# Sheet1.net
KiCad netlist of a schematic drawn in Altium Designer
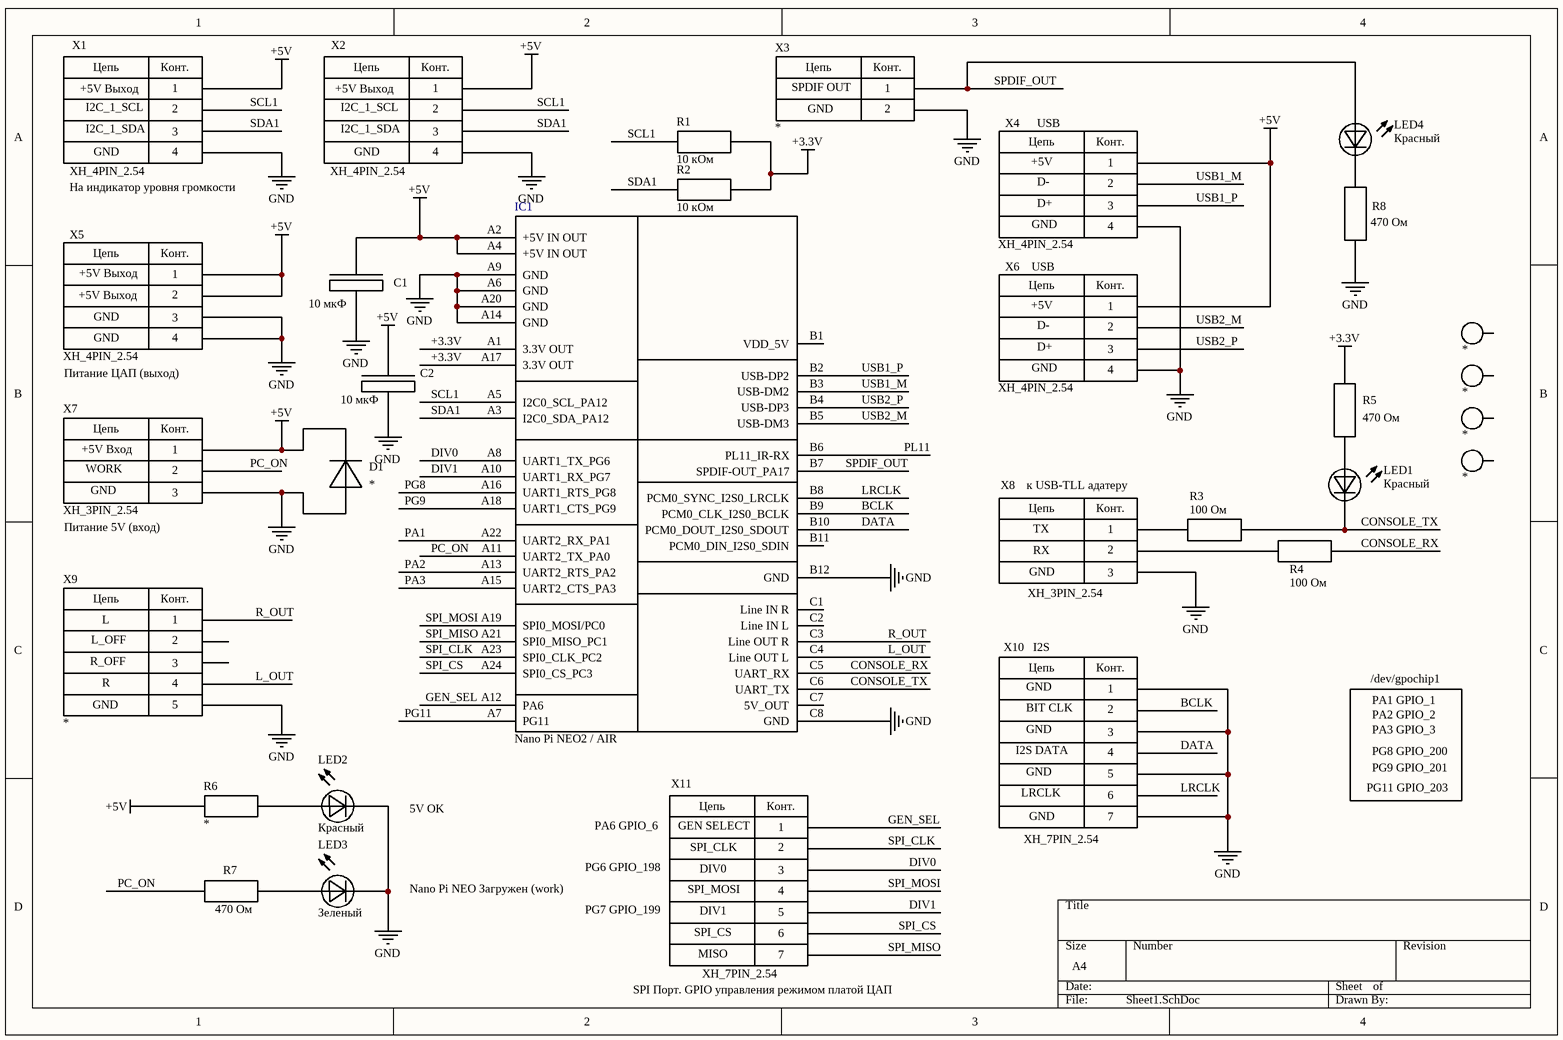
[diagram p0: Sheet1.SchDoc]

(export (version "E")
  (design (tool "Eeschema 10.0.6"))
  (components
    (comp (ref "C1")
      (value "10 мкФ")
      (footprint "Конденсатор SMD тантал 4x7")
      (libsource (lib "S83") (part "Конденсатор"))
    )
    (comp (ref "C2")
      (value "10 мкФ")
      (footprint "Конденсатор SMD тантал 4x7")
      (libsource (lib "S83") (part "Конденсатор"))
    )
    (comp (ref "D1") (value "*") (footprint "Диод SS14") (libsource (lib "S83") (part "Диод")))
    (comp (ref "H1")
      (value "*")
      (footprint "Отверстие 3,2")
      (libsource (lib "S83") (part "Отверстие монтажное"))
    )
    (comp (ref "H2")
      (value "*")
      (footprint "Отверстие 3,2")
      (libsource (lib "S83") (part "Отверстие монтажное"))
    )
    (comp (ref "H3")
      (value "*")
      (footprint "Отверстие 3,2")
      (libsource (lib "S83") (part "Отверстие монтажное"))
    )
    (comp (ref "H4")
      (value "*")
      (footprint "Отверстие 3,2")
      (libsource (lib "S83") (part "Отверстие монтажное"))
    )
    (comp (ref "IC1")
      (value "Nano Pi NEO2 / AIR")
      (footprint "NANOPI_NEO")
      (libsource (lib "S83_IC") (part "NanoPi NEO"))
    )
    (comp (ref "LED1")
      (value "Красный")
      (footprint "Светодиод 3mm")
      (libsource (lib "S83") (part "Светодиод"))
    )
    (comp (ref "LED2")
      (value "Красный")
      (footprint "Светодиод 3mm")
      (libsource (lib "S83") (part "Светодиод"))
    )
    (comp (ref "LED3")
      (value "Зеленый")
      (footprint "Светодиод 3mm")
      (libsource (lib "S83") (part "Светодиод"))
    )
    (comp (ref "LED4")
      (value "Красный")
      (footprint "Светодиод 3mm")
      (libsource (lib "S83") (part "Светодиод"))
    )
    (comp (ref "R1")
      (value "10 кОм")
      (footprint "SMD 1206 Резистор")
      (libsource (lib "S83") (part "Резистор"))
    )
    (comp (ref "R2")
      (value "10 кОм")
      (footprint "SMD 1206 Резистор")
      (libsource (lib "S83") (part "Резистор"))
    )
    (comp (ref "R3")
      (value "100 Ом")
      (footprint "SMD 1206 Резистор")
      (libsource (lib "S83") (part "Резистор"))
    )
    (comp (ref "R4")
      (value "100 Ом")
      (footprint "SMD 1206 Резистор")
      (libsource (lib "S83") (part "Резистор"))
    )
    (comp (ref "R5")
      (value "470 Ом")
      (footprint "SMD 1206 Резистор")
      (libsource (lib "S83") (part "Резистор"))
    )
    (comp (ref "R6") (value "*") (footprint "SMD 1206 Резистор") (libsource (lib "S83") (part "Резистор")))
    (comp (ref "R7")
      (value "470 Ом")
      (footprint "SMD 1206 Резистор")
      (libsource (lib "S83") (part "Резистор"))
    )
    (comp (ref "R8")
      (value "470 Ом")
      (footprint "SMD 1206 Резистор")
      (libsource (lib "S83") (part "Резистор"))
    )
    (comp (ref "X1")
      (value "XH_4PIN_2.54")
      (footprint "(1x4) PIN XH 2.54 HEADR")
      (libsource (lib "S83_connectors") (part "(1x4) pin XH 2.54 Header"))
    )
    (comp (ref "X2")
      (value "XH_4PIN_2.54")
      (footprint "(1x4) PIN XH 2.54 HEADR")
      (libsource (lib "S83_connectors") (part "(1x4) pin XH 2.54 Header"))
    )
    (comp (ref "X3")
      (value "*")
      (footprint "(1x2) PIN XH 2.54 header")
      (libsource (lib "S83_connectors") (part "(1x2)pin 2.54 Header"))
    )
    (comp (ref "X4")
      (value "XH_4PIN_2.54")
      (footprint "(1x4) PIN XH 2.54 HEADR")
      (libsource (lib "S83_connectors") (part "(1x4) pin XH 2.54 Header"))
    )
    (comp (ref "X5")
      (value "XH_4PIN_2.54")
      (footprint "(1x4) PIN XH 2.54 HEADR")
      (libsource (lib "S83_connectors") (part "(1x4) pin XH 2.54 Header"))
    )
    (comp (ref "X6")
      (value "XH_4PIN_2.54")
      (footprint "(1x4) PIN XH 2.54 HEADR")
      (libsource (lib "S83_connectors") (part "(1x4) pin XH 2.54 Header"))
    )
    (comp (ref "X7")
      (value "XH_3PIN_2.54")
      (footprint "(1x3) PIN XH 2.54 HEADR")
      (libsource (lib "S83_connectors") (part "(1x3)pin 2.54 Header"))
    )
    (comp (ref "X8")
      (value "XH_3PIN_2.54")
      (footprint "(1x3) PIN XH 2.54 HEADR")
      (libsource (lib "S83_connectors") (part "(1x3)pin 2.54 Header"))
    )
    (comp (ref "X9")
      (value "*")
      (footprint "3.5 Audio jack mama")
      (libsource (lib "S83_connectors") (part "3.5 Audio"))
    )
    (comp (ref "X10")
      (value "XH_7PIN_2.54")
      (footprint "(1x7) PIN XH 2.54 HEADR")
      (libsource (lib "S83_connectors") (part "(1x7) pin 2.54 Header"))
    )
    (comp (ref "X11")
      (value "XH_7PIN_2.54")
      (footprint "(1x7) PIN XH 2.54 HEADR")
      (libsource (lib "S83_connectors") (part "(1x7) pin 2.54 Header"))
    )
  )
  (nets
    (net (code "1") (name "+3.3V") (class "Default")
      (node (ref "IC1") (pin "A1") (pinfunction "3.3V_OUT_A1") (pintype "passive"))
      (node (ref "IC1") (pin "A17") (pinfunction "3.3V_OUT_A17") (pintype "passive"))
      (node (ref "R1") (pin "1") (pinfunction "left_1") (pintype "passive"))
      (node (ref "R2") (pin "1") (pinfunction "left_1") (pintype "passive"))
      (node (ref "R5") (pin "1") (pinfunction "left_1") (pintype "passive"))
    )
    (net (code "2") (name "+5V") (class "Default")
      (node (ref "C1") (pin "1") (pinfunction "1_1") (pintype "passive"))
      (node (ref "C2") (pin "1") (pinfunction "1_1") (pintype "passive"))
      (node (ref "D1") (pin "2") (pinfunction "K_2") (pintype "passive"))
      (node (ref "IC1") (pin "A2") (pinfunction "+5V_IN_OUT_A2") (pintype "passive"))
      (node (ref "IC1") (pin "A4") (pinfunction "+5V_IN_OUT_A4") (pintype "passive"))
      (node (ref "R6") (pin "2") (pinfunction "right_2") (pintype "passive"))
      (node (ref "X1") (pin "1") (pinfunction "1_1") (pintype "passive"))
      (node (ref "X2") (pin "1") (pinfunction "1_1") (pintype "passive"))
      (node (ref "X4") (pin "1") (pinfunction "1_1") (pintype "passive"))
      (node (ref "X5") (pin "1") (pinfunction "1_1") (pintype "passive"))
      (node (ref "X5") (pin "2") (pinfunction "2_2") (pintype "passive"))
      (node (ref "X6") (pin "1") (pinfunction "1_1") (pintype "passive"))
      (node (ref "X7") (pin "1") (pinfunction "1_1") (pintype "passive"))
    )
    (net (code "3") (name "/BCLK") (class "Default")
      (node (ref "IC1") (pin "B9") (pinfunction "PCM0_CLK_I2S0_BCLK_B9") (pintype "passive"))
      (node (ref "X10") (pin "2") (pinfunction "2_2") (pintype "passive"))
    )
    (net (code "4") (name "/CONSOLE_RX") (class "Default")
      (node (ref "IC1") (pin "C5") (pinfunction "UART_RX_C5") (pintype "passive"))
      (node (ref "R4") (pin "1") (pinfunction "left_1") (pintype "passive"))
    )
    (net (code "5") (name "/CONSOLE_TX") (class "Default")
      (node (ref "IC1") (pin "C6") (pinfunction "UART_TX_C6") (pintype "passive"))
      (node (ref "LED1") (pin "2") (pinfunction "K_2") (pintype "passive"))
      (node (ref "R3") (pin "1") (pinfunction "left_1") (pintype "passive"))
    )
    (net (code "8") (name "/DATA") (class "Default")
      (node (ref "IC1") (pin "B10") (pinfunction "PCM0_DOUT_I2S0_SDOUT_B10") (pintype "passive"))
      (node (ref "X10") (pin "4") (pinfunction "4_4") (pintype "passive"))
    )
    (net (code "9") (name "/DIV0") (class "Default")
      (node (ref "IC1") (pin "A8") (pinfunction "UART1_TX_PG6_A8") (pintype "passive"))
      (node (ref "X11") (pin "3") (pinfunction "3_3") (pintype "passive"))
    )
    (net (code "10") (name "/DIV1") (class "Default")
      (node (ref "IC1") (pin "A10") (pinfunction "UART1_RX_PG7_A10") (pintype "passive"))
      (node (ref "X11") (pin "5") (pinfunction "5_5") (pintype "passive"))
    )
    (net (code "11") (name "/GEN_SEL") (class "Default")
      (node (ref "IC1") (pin "A12") (pinfunction "PA6_A12") (pintype "passive"))
      (node (ref "X11") (pin "1") (pinfunction "1_1") (pintype "passive"))
    )
    (net (code "14") (name "/LRCLK") (class "Default")
      (node (ref "IC1") (pin "B8") (pinfunction "PCM0_SYNC_I2S0_LRCLK_B8") (pintype "passive"))
      (node (ref "X10") (pin "6") (pinfunction "6_6") (pintype "passive"))
    )
    (net (code "15") (name "/L_OUT") (class "Default")
      (node (ref "IC1") (pin "C4") (pinfunction "Line_OUT_L_C4") (pintype "passive"))
      (node (ref "X9") (pin "4") (pinfunction "4_4") (pintype "passive"))
    )
    (net (code "16") (name "/PA1") (class "Default")
      (node (ref "IC1") (pin "A22") (pinfunction "UART2_RX_PA1_A22") (pintype "passive"))
    )
    (net (code "17") (name "/PA2") (class "Default")
      (node (ref "IC1") (pin "A13") (pinfunction "UART2_RTS_PA2_A13") (pintype "passive"))
    )
    (net (code "18") (name "/PA3") (class "Default")
      (node (ref "IC1") (pin "A15") (pinfunction "UART2_CTS_PA3_A15") (pintype "passive"))
    )
    (net (code "19") (name "/PC_ON") (class "Default")
      (node (ref "IC1") (pin "A11") (pinfunction "UART2_TX_PA0_A11") (pintype "passive"))
      (node (ref "R7") (pin "2") (pinfunction "right_2") (pintype "passive"))
      (node (ref "X7") (pin "2") (pinfunction "2_2") (pintype "passive"))
    )
    (net (code "20") (name "/PG8") (class "Default")
      (node (ref "IC1") (pin "A16") (pinfunction "UART1_RTS_PG8_A16") (pintype "passive"))
    )
    (net (code "21") (name "/PG9") (class "Default")
      (node (ref "IC1") (pin "A18") (pinfunction "UART1_CTS_PG9_A18") (pintype "passive"))
    )
    (net (code "22") (name "/PG11") (class "Default")
      (node (ref "IC1") (pin "A7") (pinfunction "PG11_A7") (pintype "passive"))
    )
    (net (code "23") (name "/PL11") (class "Default")
      (node (ref "IC1") (pin "B6") (pinfunction "PL11_IR-RX_B6") (pintype "passive"))
    )
    (net (code "24") (name "/R_OUT") (class "Default")
      (node (ref "IC1") (pin "C3") (pinfunction "Line_OUT_R_C3") (pintype "passive"))
      (node (ref "X9") (pin "1") (pinfunction "1_1") (pintype "passive"))
    )
    (net (code "25") (name "/SCL1") (class "Default")
      (node (ref "IC1") (pin "A5") (pinfunction "I2C0_SCL_PA12_A5") (pintype "passive"))
      (node (ref "R1") (pin "2") (pinfunction "right_2") (pintype "passive"))
      (node (ref "X1") (pin "2") (pinfunction "2_2") (pintype "passive"))
      (node (ref "X2") (pin "2") (pinfunction "2_2") (pintype "passive"))
    )
    (net (code "26") (name "/SDA1") (class "Default")
      (node (ref "IC1") (pin "A3") (pinfunction "I2C0_SDA_PA12_A3") (pintype "passive"))
      (node (ref "R2") (pin "2") (pinfunction "right_2") (pintype "passive"))
      (node (ref "X1") (pin "3") (pinfunction "3_3") (pintype "passive"))
      (node (ref "X2") (pin "3") (pinfunction "3_3") (pintype "passive"))
    )
    (net (code "27") (name "/SPDIF_OUT") (class "Default")
      (node (ref "IC1") (pin "B7") (pinfunction "SPDIF-OUT_PA17_B7") (pintype "passive"))
      (node (ref "LED4") (pin "1") (pinfunction "А_1") (pintype "passive"))
      (node (ref "X3") (pin "1") (pinfunction "1_1") (pintype "passive"))
    )
    (net (code "28") (name "/SPI_CLK") (class "Default")
      (node (ref "IC1") (pin "A23") (pinfunction "SPI0_CLK_PC2_A23") (pintype "passive"))
      (node (ref "X11") (pin "2") (pinfunction "2_2") (pintype "passive"))
    )
    (net (code "29") (name "/SPI_CS") (class "Default")
      (node (ref "IC1") (pin "A24") (pinfunction "SPI0_CS_PC3_A24") (pintype "passive"))
      (node (ref "X11") (pin "6") (pinfunction "6_6") (pintype "passive"))
    )
    (net (code "30") (name "/SPI_MISO") (class "Default")
      (node (ref "IC1") (pin "A21") (pinfunction "SPI0_MISO_PC1_A21") (pintype "passive"))
      (node (ref "X11") (pin "7") (pinfunction "7_7") (pintype "passive"))
    )
    (net (code "31") (name "/SPI_MOSI") (class "Default")
      (node (ref "IC1") (pin "A19") (pinfunction "SPI0_MOSI/PС0_A19") (pintype "passive"))
      (node (ref "X11") (pin "4") (pinfunction "4_4") (pintype "passive"))
    )
    (net (code "32") (name "/USB1_M") (class "Default")
      (node (ref "IC1") (pin "B3") (pinfunction "USB-DM2_B3") (pintype "passive"))
      (node (ref "X4") (pin "2") (pinfunction "2_2") (pintype "passive"))
    )
    (net (code "33") (name "/USB1_P") (class "Default")
      (node (ref "IC1") (pin "B2") (pinfunction "USB-DP2_B2") (pintype "passive"))
      (node (ref "X4") (pin "3") (pinfunction "3_3") (pintype "passive"))
    )
    (net (code "34") (name "/USB2_M") (class "Default")
      (node (ref "IC1") (pin "B5") (pinfunction "USB-DM3_B5") (pintype "passive"))
      (node (ref "X6") (pin "2") (pinfunction "2_2") (pintype "passive"))
    )
    (net (code "35") (name "/USB2_P") (class "Default")
      (node (ref "IC1") (pin "B4") (pinfunction "USB-DP3_B4") (pintype "passive"))
      (node (ref "X6") (pin "3") (pinfunction "3_3") (pintype "passive"))
    )
    (net (code "36") (name "GND") (class "Default")
      (node (ref "C1") (pin "2") (pinfunction "2_2") (pintype "passive"))
      (node (ref "C2") (pin "2") (pinfunction "2_2") (pintype "passive"))
      (node (ref "D1") (pin "1") (pinfunction "А_1") (pintype "passive"))
      (node (ref "IC1") (pin "A14") (pinfunction "GND_A14") (pintype "passive"))
      (node (ref "IC1") (pin "A20") (pinfunction "GND_A20") (pintype "passive"))
      (node (ref "IC1") (pin "A6") (pinfunction "GND_A6") (pintype "passive"))
      (node (ref "IC1") (pin "A9") (pinfunction "GND_A9") (pintype "passive"))
      (node (ref "IC1") (pin "B12") (pinfunction "GND_B12") (pintype "passive"))
      (node (ref "IC1") (pin "C8") (pinfunction "GND_C8") (pintype "passive"))
      (node (ref "LED2") (pin "2") (pinfunction "K_2") (pintype "passive"))
      (node (ref "LED3") (pin "2") (pinfunction "K_2") (pintype "passive"))
      (node (ref "R8") (pin "2") (pinfunction "right_2") (pintype "passive"))
      (node (ref "X1") (pin "4") (pinfunction "4_4") (pintype "passive"))
      (node (ref "X10") (pin "1") (pinfunction "1_1") (pintype "passive"))
      (node (ref "X10") (pin "3") (pinfunction "3_3") (pintype "passive"))
      (node (ref "X10") (pin "5") (pinfunction "5_5") (pintype "passive"))
      (node (ref "X10") (pin "7") (pinfunction "7_7") (pintype "passive"))
      (node (ref "X2") (pin "4") (pinfunction "4_4") (pintype "passive"))
      (node (ref "X3") (pin "2") (pinfunction "2_2") (pintype "passive"))
      (node (ref "X4") (pin "4") (pinfunction "4_4") (pintype "passive"))
      (node (ref "X5") (pin "3") (pinfunction "3_3") (pintype "passive"))
      (node (ref "X5") (pin "4") (pinfunction "4_4") (pintype "passive"))
      (node (ref "X6") (pin "4") (pinfunction "4_4") (pintype "passive"))
      (node (ref "X7") (pin "3") (pinfunction "3_3") (pintype "passive"))
      (node (ref "X8") (pin "3") (pinfunction "3_3") (pintype "passive"))
      (node (ref "X9") (pin "5") (pinfunction "5_5") (pintype "passive"))
    )
    (net (code "37") (name "Net-(LED1-А)") (class "Default")
      (node (ref "LED1") (pin "1") (pinfunction "А_1") (pintype "passive"))
      (node (ref "R5") (pin "2") (pinfunction "right_2") (pintype "passive"))
    )
    (net (code "38") (name "Net-(LED2-А)") (class "Default")
      (node (ref "LED2") (pin "1") (pinfunction "А_1") (pintype "passive"))
      (node (ref "R6") (pin "1") (pinfunction "left_1") (pintype "passive"))
    )
    (net (code "39") (name "Net-(LED3-А)") (class "Default")
      (node (ref "LED3") (pin "1") (pinfunction "А_1") (pintype "passive"))
      (node (ref "R7") (pin "1") (pinfunction "left_1") (pintype "passive"))
    )
    (net (code "40") (name "Net-(LED4-K)") (class "Default")
      (node (ref "LED4") (pin "2") (pinfunction "K_2") (pintype "passive"))
      (node (ref "R8") (pin "1") (pinfunction "left_1") (pintype "passive"))
    )
    (net (code "41") (name "Net-(R3-right)") (class "Default")
      (node (ref "R3") (pin "2") (pinfunction "right_2") (pintype "passive"))
      (node (ref "X8") (pin "1") (pinfunction "1_1") (pintype "passive"))
    )
    (net (code "42") (name "Net-(R4-right)") (class "Default")
      (node (ref "R4") (pin "2") (pinfunction "right_2") (pintype "passive"))
      (node (ref "X8") (pin "2") (pinfunction "2_2") (pintype "passive"))
    )
    (net (code "43") (name "unconnected-(H1-Pad1)") (class "Default")
      (node (ref "H1") (pin "1") (pinfunction "1_1") (pintype "passive"))
    )
    (net (code "44") (name "unconnected-(H2-Pad1)") (class "Default")
      (node (ref "H2") (pin "1") (pinfunction "1_1") (pintype "passive"))
    )
    (net (code "45") (name "unconnected-(H3-Pad1)") (class "Default")
      (node (ref "H3") (pin "1") (pinfunction "1_1") (pintype "passive"))
    )
    (net (code "46") (name "unconnected-(H4-Pad1)") (class "Default")
      (node (ref "H4") (pin "1") (pinfunction "1_1") (pintype "passive"))
    )
    (net (code "47") (name "unconnected-(IC1-5V_OUT-PadC7)") (class "Default")
      (node (ref "IC1") (pin "C7") (pinfunction "5V_OUT_C7") (pintype "passive"))
    )
    (net (code "48") (name "unconnected-(IC1-Line_IN_L-PadC2)") (class "Default")
      (node (ref "IC1") (pin "C2") (pinfunction "Line_IN_L_C2") (pintype "passive"))
    )
    (net (code "49") (name "unconnected-(IC1-Line_IN_R-PadC1)") (class "Default")
      (node (ref "IC1") (pin "C1") (pinfunction "Line_IN_R_C1") (pintype "passive"))
    )
    (net (code "50") (name "unconnected-(IC1-PCM0_DIN_I2S0_SDIN-PadB11)") (class "Default")
      (node (ref "IC1") (pin "B11") (pinfunction "PCM0_DIN_I2S0_SDIN_B11") (pintype "passive"))
    )
    (net (code "51") (name "unconnected-(IC1-VDD_5V-PadB1)") (class "Default")
      (node (ref "IC1") (pin "B1") (pinfunction "VDD_5V_B1") (pintype "passive"))
    )
    (net (code "52") (name "unconnected-(X9-Pad2)") (class "Default")
      (node (ref "X9") (pin "2") (pinfunction "2_2") (pintype "passive"))
    )
    (net (code "53") (name "unconnected-(X9-Pad3)") (class "Default")
      (node (ref "X9") (pin "3") (pinfunction "3_3") (pintype "passive"))
    )
  )
)
